# eCog116_Pi_RGB_Matrix.net
KiCad netlist of a schematic drawn in EAGLE
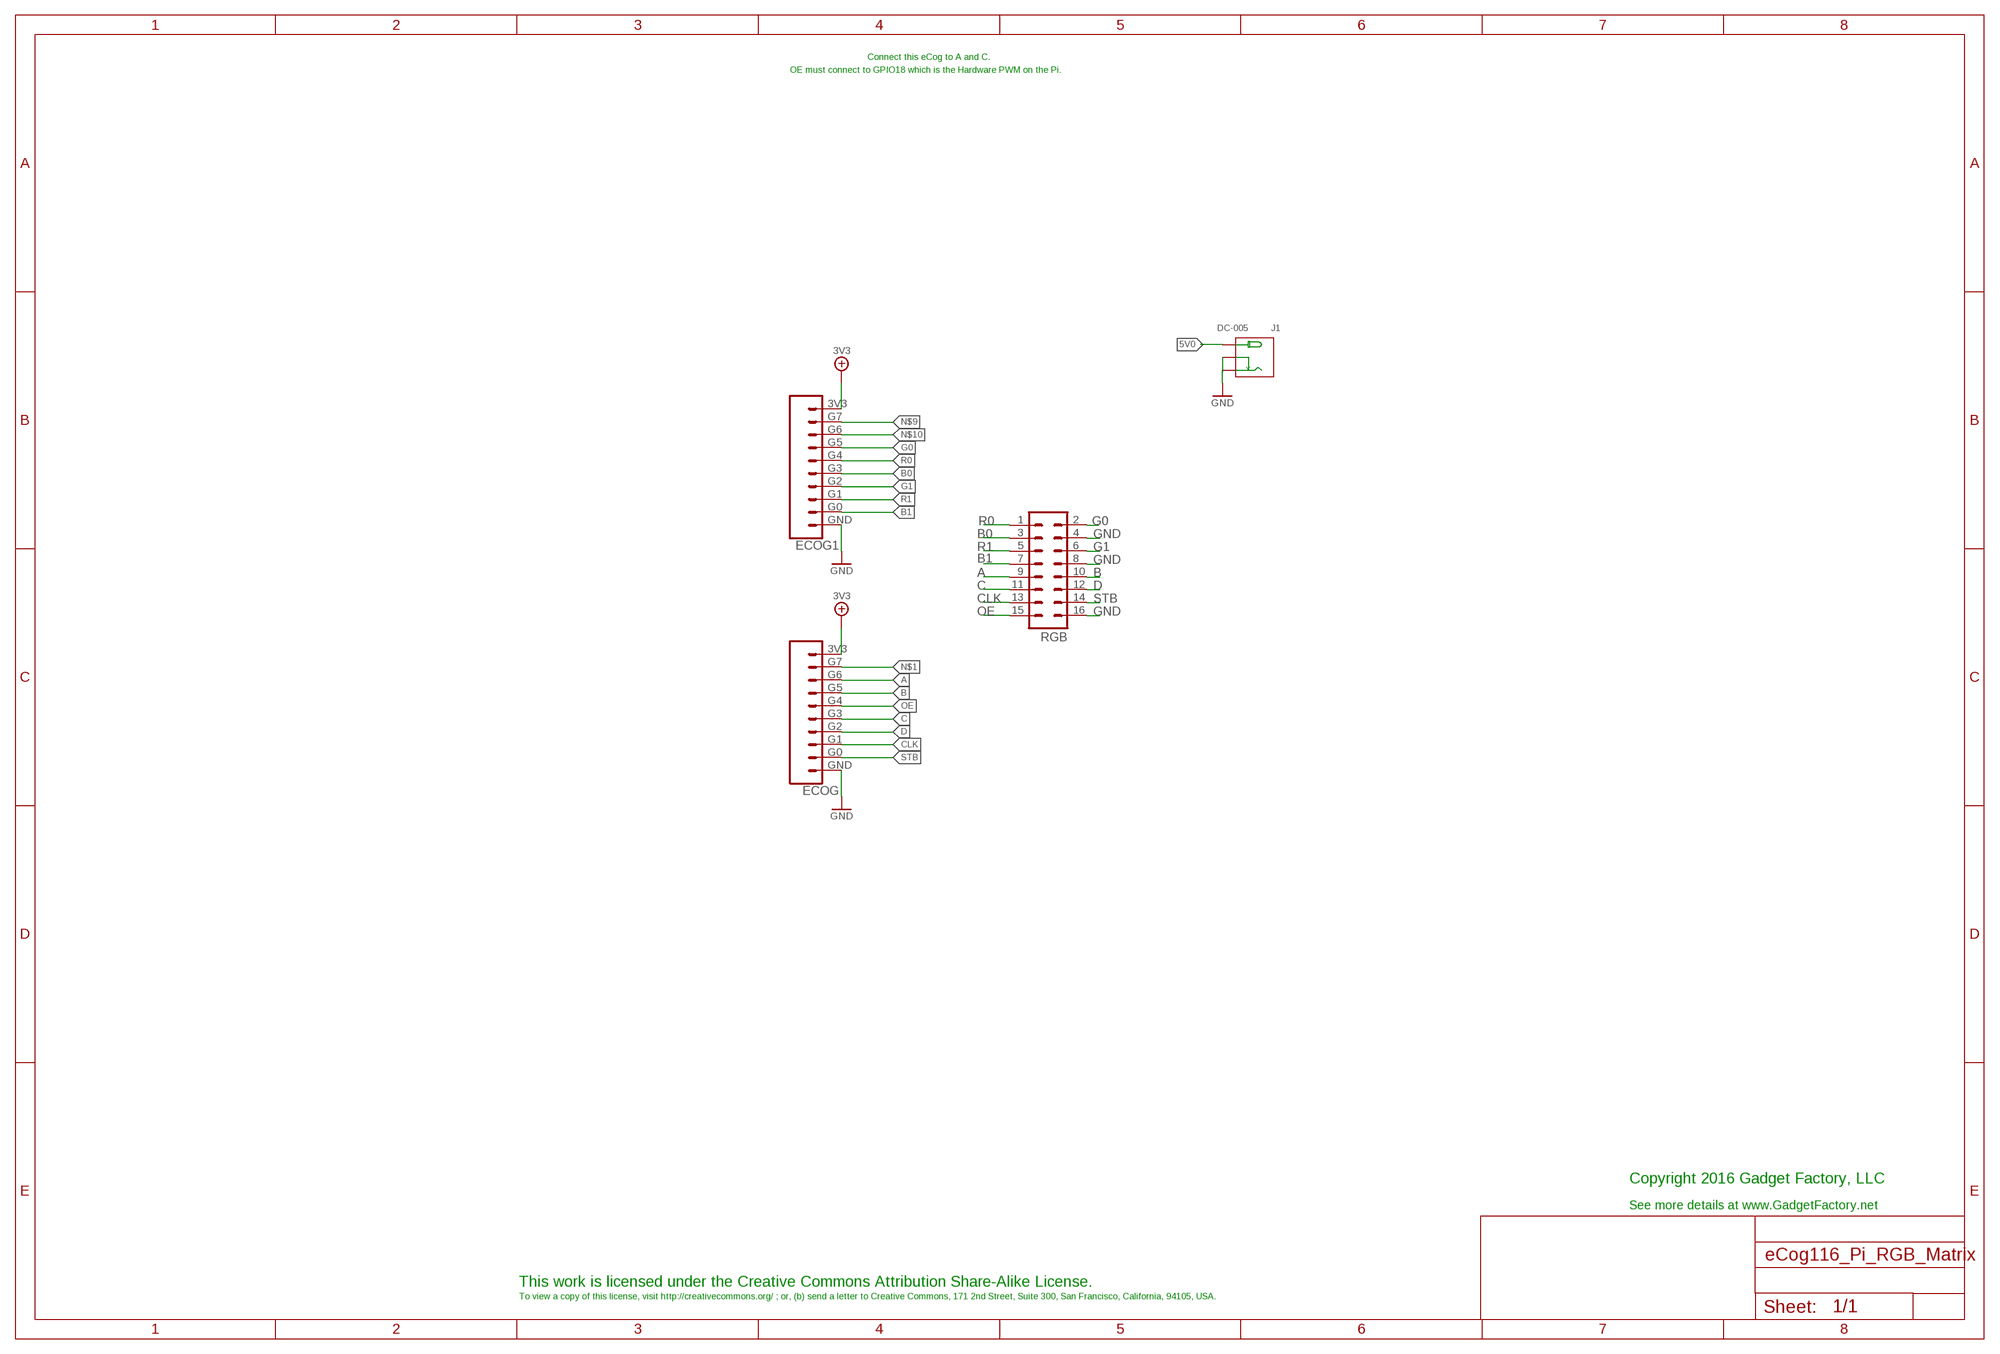
[diagram p0: schematic, sheet 1]

(export (version "E")
  (design (tool "Eeschema 10.0.6"))
  (components
    (comp (ref "ECOG")
      (value "ECOG_GENERAL_ROWTHROUGHOLE")
      (footprint "eagle-import:ECOG_GENERAL_TH")
      (libsource (lib "eagle-import") (part "ECOG_GENERAL_ROWTHROUGHOLE"))
    )
    (comp (ref "ECOG1")
      (value "ECOG_GENERAL_ROWTHROUGHOLE")
      (footprint "eagle-import:ECOG_GENERAL_TH")
      (libsource (lib "eagle-import") (part "ECOG_GENERAL_ROWTHROUGHOLE"))
    )
    (comp (ref "J1")
      (value "DC-005")
      (footprint "eagle-import:DCJ3P-14.2X11.0X9.0MM")
      (libsource (lib "eagle-import") (part "CONN-POWER-JACK-2.1MM(DC-005)"))
    )
    (comp (ref "RGB")
      (value "ML16")
      (footprint "eagle-import:ML16")
      (fields (field (name "PARTNO") "PRPC004DAAN-RC"))
      (libsource (lib "eagle-import") (part "ML16"))
    )
  )
  (nets
    (net (code "1") (name "3V3") (class "Default")
      (node (ref "ECOG") (pin "3V3") (pinfunction "3V3_3V3") (pintype "power_in"))
      (node (ref "ECOG1") (pin "3V3") (pinfunction "3V3_3V3") (pintype "power_in"))
    )
    (net (code "2") (name "5V0") (class "Default")
      (node (ref "J1") (pin "+") (pinfunction "+_+") (pintype "bidirectional"))
    )
    (net (code "3") (name "A") (class "Default")
      (node (ref "ECOG") (pin "G6") (pinfunction "G6_G6") (pintype "passive"))
      (node (ref "RGB") (pin "9") (pinfunction "9_9") (pintype "passive"))
    )
    (net (code "4") (name "B") (class "Default")
      (node (ref "ECOG") (pin "G5") (pinfunction "G5_G5") (pintype "passive"))
      (node (ref "RGB") (pin "10") (pinfunction "10_10") (pintype "passive"))
    )
    (net (code "5") (name "B0") (class "Default")
      (node (ref "ECOG1") (pin "G3") (pinfunction "G3_G3") (pintype "passive"))
      (node (ref "RGB") (pin "3") (pinfunction "3_3") (pintype "passive"))
    )
    (net (code "6") (name "B1") (class "Default")
      (node (ref "ECOG1") (pin "G0") (pinfunction "G0_G0") (pintype "passive"))
      (node (ref "RGB") (pin "7") (pinfunction "7_7") (pintype "passive"))
    )
    (net (code "7") (name "C") (class "Default")
      (node (ref "ECOG") (pin "G3") (pinfunction "G3_G3") (pintype "passive"))
      (node (ref "RGB") (pin "11") (pinfunction "11_11") (pintype "passive"))
    )
    (net (code "8") (name "CLK") (class "Default")
      (node (ref "ECOG") (pin "G1") (pinfunction "G1_G1") (pintype "passive"))
      (node (ref "RGB") (pin "13") (pinfunction "13_13") (pintype "passive"))
    )
    (net (code "9") (name "D") (class "Default")
      (node (ref "ECOG") (pin "G2") (pinfunction "G2_G2") (pintype "passive"))
      (node (ref "RGB") (pin "12") (pinfunction "12_12") (pintype "passive"))
    )
    (net (code "10") (name "G0") (class "Default")
      (node (ref "ECOG1") (pin "G5") (pinfunction "G5_G5") (pintype "passive"))
      (node (ref "RGB") (pin "2") (pinfunction "2_2") (pintype "passive"))
    )
    (net (code "11") (name "G1") (class "Default")
      (node (ref "ECOG1") (pin "G2") (pinfunction "G2_G2") (pintype "passive"))
      (node (ref "RGB") (pin "6") (pinfunction "6_6") (pintype "passive"))
    )
    (net (code "12") (name "GND") (class "Default")
      (node (ref "ECOG") (pin "GND") (pinfunction "GND_GND") (pintype "power_in"))
      (node (ref "ECOG1") (pin "GND") (pinfunction "GND_GND") (pintype "power_in"))
      (node (ref "J1") (pin "-1") (pinfunction "-_-1") (pintype "bidirectional"))
      (node (ref "J1") (pin "-2") (pinfunction "CDN_-2") (pintype "bidirectional"))
      (node (ref "RGB") (pin "16") (pinfunction "16_16") (pintype "passive"))
      (node (ref "RGB") (pin "4") (pinfunction "4_4") (pintype "passive"))
      (node (ref "RGB") (pin "8") (pinfunction "8_8") (pintype "passive"))
    )
    (net (code "13") (name "N$1") (class "Default")
      (node (ref "ECOG") (pin "G7") (pinfunction "G7_G7") (pintype "passive"))
    )
    (net (code "14") (name "N$9") (class "Default")
      (node (ref "ECOG1") (pin "G7") (pinfunction "G7_G7") (pintype "passive"))
    )
    (net (code "15") (name "N$10") (class "Default")
      (node (ref "ECOG1") (pin "G6") (pinfunction "G6_G6") (pintype "passive"))
    )
    (net (code "16") (name "OE") (class "Default")
      (node (ref "ECOG") (pin "G4") (pinfunction "G4_G4") (pintype "passive"))
      (node (ref "RGB") (pin "15") (pinfunction "15_15") (pintype "passive"))
    )
    (net (code "17") (name "R0") (class "Default")
      (node (ref "ECOG1") (pin "G4") (pinfunction "G4_G4") (pintype "passive"))
      (node (ref "RGB") (pin "1") (pinfunction "1_1") (pintype "passive"))
    )
    (net (code "18") (name "R1") (class "Default")
      (node (ref "ECOG1") (pin "G1") (pinfunction "G1_G1") (pintype "passive"))
      (node (ref "RGB") (pin "5") (pinfunction "5_5") (pintype "passive"))
    )
    (net (code "19") (name "STB") (class "Default")
      (node (ref "ECOG") (pin "G0") (pinfunction "G0_G0") (pintype "passive"))
      (node (ref "RGB") (pin "14") (pinfunction "14_14") (pintype "passive"))
    )
  )
)
